# phare.net
KiCad netlist of a schematic drawn in EAGLE
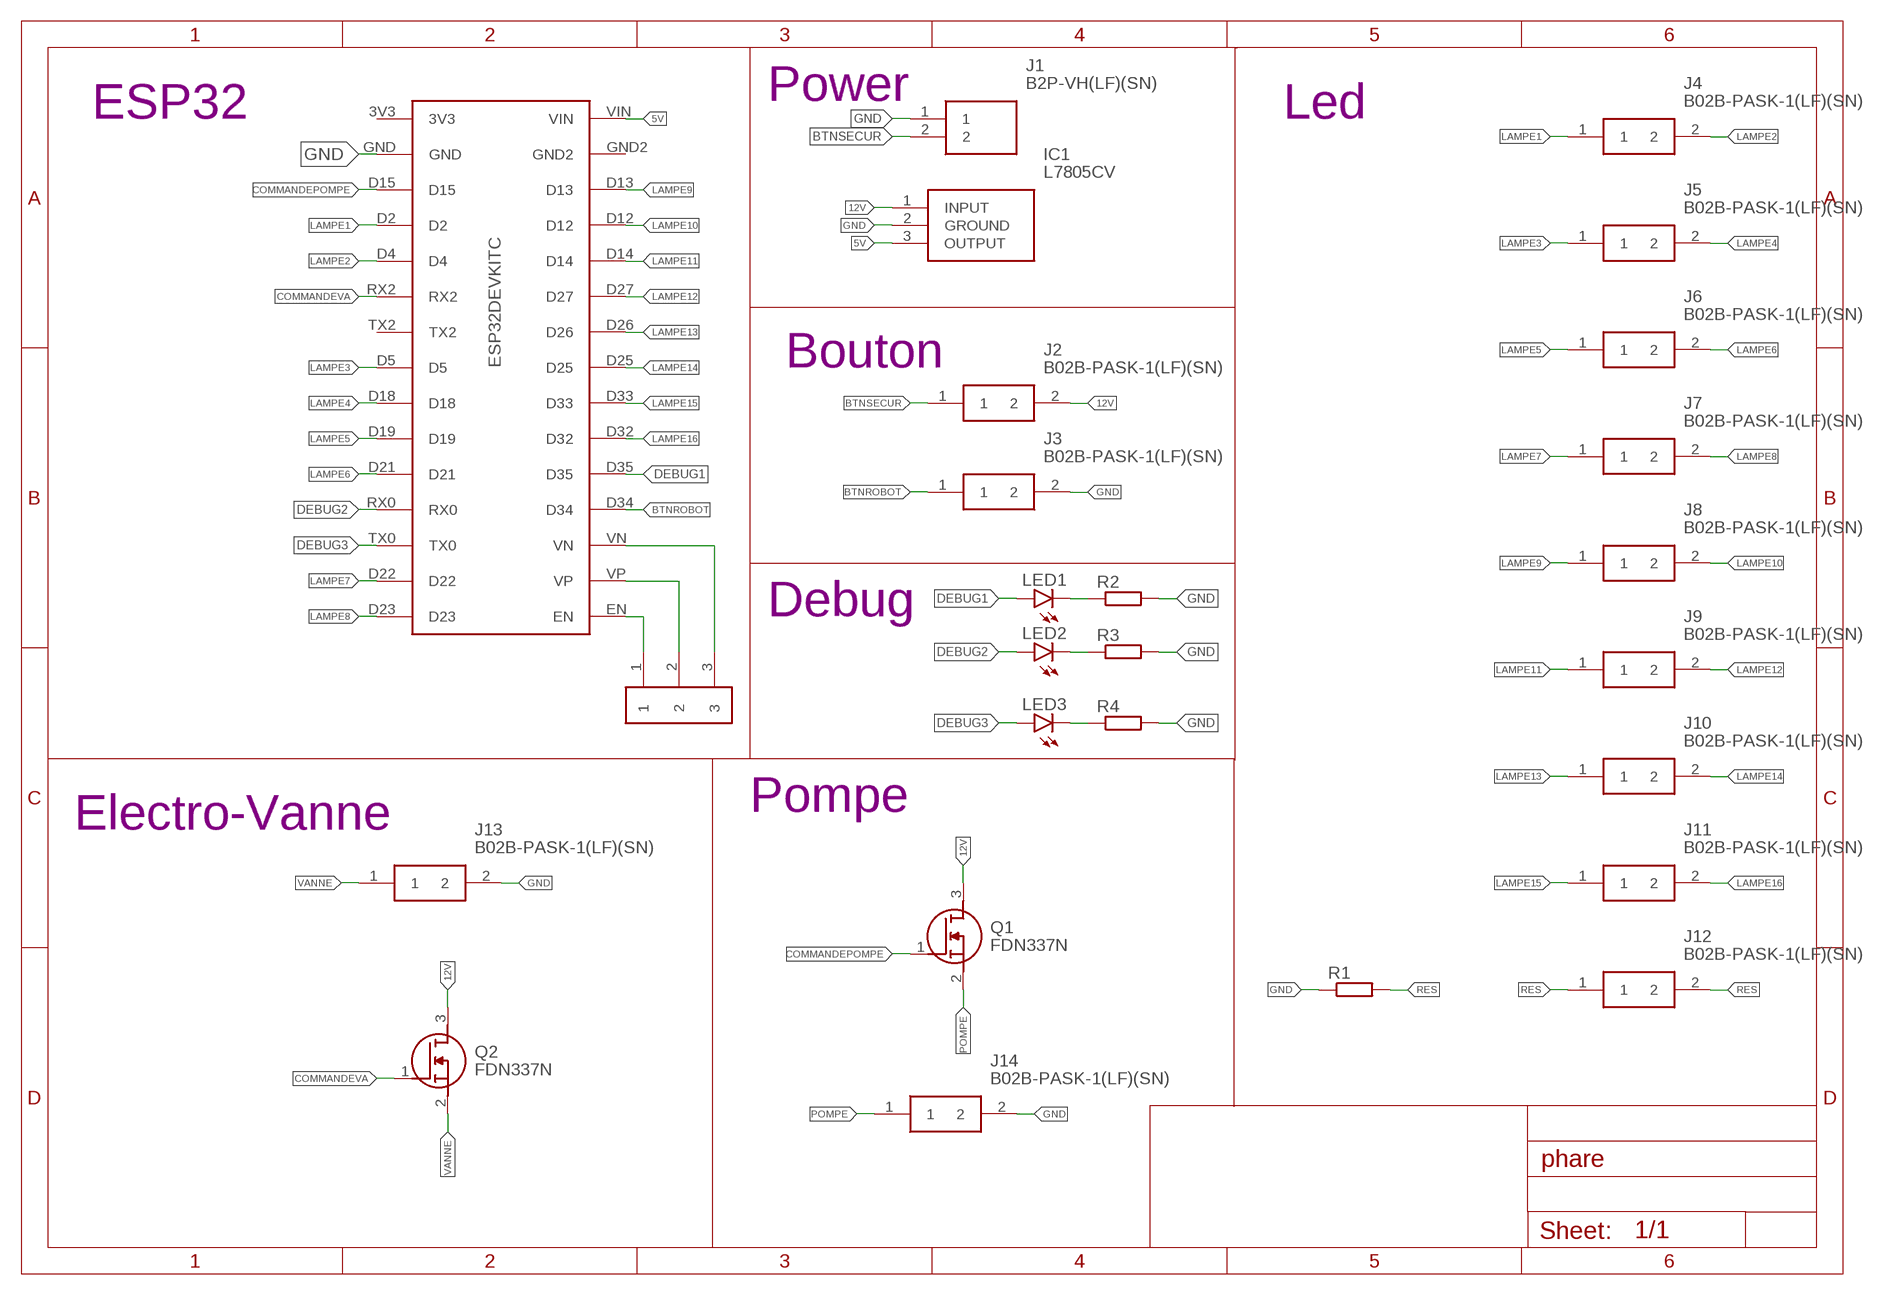
[diagram p0: schematic, sheet 1]

(export (version "E")
  (design (tool "Eeschema 10.0.6"))
  (components
    (comp (ref "IC1")
      (value "L7805CV")
      (footprint "eagle-import:TO255P460X1020X2008-3P")
      (fields (field (name "MOUSER_PART_NUMBER") "511-L7805CV"))
      (libsource (lib "eagle-import") (part "L7805CV"))
    )
    (comp (ref "J1")
      (value "B2P-VH(LF)(SN)")
      (footprint "eagle-import:SHDR2W114P0X396_1X2_786X850X94")
      (fields (field (name "RS_PART_NUMBER") "8201147P"))
      (libsource (lib "eagle-import") (part "B2P-VH(LF)(SN)"))
    )
    (comp (ref "J2")
      (value "B02B-PASK-1(LF)(SN)")
      (footprint "eagle-import:B02BPASK1LFSN")
      (libsource (lib "eagle-import") (part "B02B-PASK-1(LF)(SN)"))
    )
    (comp (ref "J3")
      (value "B02B-PASK-1(LF)(SN)")
      (footprint "eagle-import:B02BPASK1LFSN")
      (libsource (lib "eagle-import") (part "B02B-PASK-1(LF)(SN)"))
    )
    (comp (ref "J4")
      (value "B02B-PASK-1(LF)(SN)")
      (footprint "eagle-import:B02BPASK1LFSN")
      (libsource (lib "eagle-import") (part "B02B-PASK-1(LF)(SN)"))
    )
    (comp (ref "J5")
      (value "B02B-PASK-1(LF)(SN)")
      (footprint "eagle-import:B02BPASK1LFSN")
      (libsource (lib "eagle-import") (part "B02B-PASK-1(LF)(SN)"))
    )
    (comp (ref "J6")
      (value "B02B-PASK-1(LF)(SN)")
      (footprint "eagle-import:B02BPASK1LFSN")
      (libsource (lib "eagle-import") (part "B02B-PASK-1(LF)(SN)"))
    )
    (comp (ref "J7")
      (value "B02B-PASK-1(LF)(SN)")
      (footprint "eagle-import:B02BPASK1LFSN")
      (libsource (lib "eagle-import") (part "B02B-PASK-1(LF)(SN)"))
    )
    (comp (ref "J8")
      (value "B02B-PASK-1(LF)(SN)")
      (footprint "eagle-import:B02BPASK1LFSN")
      (libsource (lib "eagle-import") (part "B02B-PASK-1(LF)(SN)"))
    )
    (comp (ref "J9")
      (value "B02B-PASK-1(LF)(SN)")
      (footprint "eagle-import:B02BPASK1LFSN")
      (libsource (lib "eagle-import") (part "B02B-PASK-1(LF)(SN)"))
    )
    (comp (ref "J10")
      (value "B02B-PASK-1(LF)(SN)")
      (footprint "eagle-import:B02BPASK1LFSN")
      (libsource (lib "eagle-import") (part "B02B-PASK-1(LF)(SN)"))
    )
    (comp (ref "J11")
      (value "B02B-PASK-1(LF)(SN)")
      (footprint "eagle-import:B02BPASK1LFSN")
      (libsource (lib "eagle-import") (part "B02B-PASK-1(LF)(SN)"))
    )
    (comp (ref "J12")
      (value "B02B-PASK-1(LF)(SN)")
      (footprint "eagle-import:B02BPASK1LFSN")
      (libsource (lib "eagle-import") (part "B02B-PASK-1(LF)(SN)"))
    )
    (comp (ref "J13")
      (value "B02B-PASK-1(LF)(SN)")
      (footprint "eagle-import:B02BPASK1LFSN")
      (libsource (lib "eagle-import") (part "B02B-PASK-1(LF)(SN)"))
    )
    (comp (ref "J14")
      (value "B02B-PASK-1(LF)(SN)")
      (footprint "eagle-import:B02BPASK1LFSN")
      (libsource (lib "eagle-import") (part "B02B-PASK-1(LF)(SN)"))
    )
    (comp (ref "LED1")
      (value "LEDCHIP-LED0805")
      (footprint "eagle-import:CHIP-LED0805")
      (libsource (lib "eagle-import") (part "LEDCHIP-LED0805"))
    )
    (comp (ref "LED2")
      (value "LEDCHIP-LED0805")
      (footprint "eagle-import:CHIP-LED0805")
      (libsource (lib "eagle-import") (part "LEDCHIP-LED0805"))
    )
    (comp (ref "LED3")
      (value "LEDCHIP-LED0805")
      (footprint "eagle-import:CHIP-LED0805")
      (libsource (lib "eagle-import") (part "LEDCHIP-LED0805"))
    )
    (comp (ref "Q1")
      (value "FDN337N")
      (footprint "eagle-import:SOT95P237X112-3N")
      (fields (field (name "MOUSER_PART_NUMBER") "512-FDN337N") (field (name "RS_PART_NUMBER") "6710429P"))
      (libsource (lib "eagle-import") (part "FDN337N"))
    )
    (comp (ref "Q2")
      (value "FDN337N")
      (footprint "eagle-import:SOT95P237X112-3N")
      (fields (field (name "MOUSER_PART_NUMBER") "512-FDN337N") (field (name "RS_PART_NUMBER") "6710429P"))
      (libsource (lib "eagle-import") (part "FDN337N"))
    )
    (comp (ref "R1")
      (value "R-EU_R0805")
      (footprint "eagle-import:R0805")
      (libsource (lib "eagle-import") (part "R-EU_R0805"))
    )
    (comp (ref "R2")
      (value "R-EU_R0805")
      (footprint "eagle-import:R0805")
      (libsource (lib "eagle-import") (part "R-EU_R0805"))
    )
    (comp (ref "R3")
      (value "R-EU_R0805")
      (footprint "eagle-import:R0805")
      (libsource (lib "eagle-import") (part "R-EU_R0805"))
    )
    (comp (ref "R4")
      (value "R-EU_R0805")
      (footprint "eagle-import:R0805")
      (libsource (lib "eagle-import") (part "R-EU_R0805"))
    )
    (comp (ref "U$1")
      (value "ESP32DEVKITC")
      (footprint "eagle-import:ESP32FOOTPRINT")
      (libsource (lib "eagle-import") (part "ESP32DEVKITC"))
    )
    (comp (ref "U$2")
      (value "HEADER3PIN")
      (footprint "eagle-import:HEADER3PINFOOTPRINT")
      (libsource (lib "eagle-import") (part "HEADER3PIN"))
    )
  )
  (nets
    (net (code "1") (name "5V") (class "Default")
      (node (ref "IC1") (pin "3") (pinfunction "OUTPUT_3") (pintype "bidirectional"))
      (node (ref "U$1") (pin "VIN") (pinfunction "VIN_VIN") (pintype "bidirectional"))
    )
    (net (code "2") (name "12V") (class "Default")
      (node (ref "IC1") (pin "1") (pinfunction "INPUT_1") (pintype "bidirectional"))
      (node (ref "J2") (pin "2") (pinfunction "2_2") (pintype "bidirectional"))
      (node (ref "Q1") (pin "3") (pinfunction "D_3") (pintype "bidirectional"))
      (node (ref "Q2") (pin "3") (pinfunction "D_3") (pintype "bidirectional"))
    )
    (net (code "3") (name "BTNROBOT") (class "Default")
      (node (ref "J3") (pin "1") (pinfunction "1_1") (pintype "bidirectional"))
      (node (ref "U$1") (pin "D34") (pinfunction "D34_D34") (pintype "bidirectional"))
    )
    (net (code "4") (name "BTNSECUR") (class "Default")
      (node (ref "J1") (pin "2") (pinfunction "2_2") (pintype "bidirectional"))
      (node (ref "J2") (pin "1") (pinfunction "1_1") (pintype "bidirectional"))
    )
    (net (code "5") (name "COMMANDEPOMPE") (class "Default")
      (node (ref "Q1") (pin "1") (pinfunction "G_1") (pintype "bidirectional"))
      (node (ref "U$1") (pin "D15") (pinfunction "D15_D15") (pintype "bidirectional"))
    )
    (net (code "6") (name "COMMANDEVA") (class "Default")
      (node (ref "Q2") (pin "1") (pinfunction "G_1") (pintype "bidirectional"))
      (node (ref "U$1") (pin "RX2") (pinfunction "RX2_RX2") (pintype "bidirectional"))
    )
    (net (code "7") (name "DEBUG1") (class "Default")
      (node (ref "LED1") (pin "A") (pinfunction "A_A") (pintype "passive"))
      (node (ref "U$1") (pin "D35") (pinfunction "D35_D35") (pintype "bidirectional"))
    )
    (net (code "8") (name "DEBUG2") (class "Default")
      (node (ref "LED2") (pin "A") (pinfunction "A_A") (pintype "passive"))
      (node (ref "U$1") (pin "RX0") (pinfunction "RX0_RX0") (pintype "bidirectional"))
    )
    (net (code "9") (name "DEBUG3") (class "Default")
      (node (ref "LED3") (pin "A") (pinfunction "A_A") (pintype "passive"))
      (node (ref "U$1") (pin "TX0") (pinfunction "TX0_TX0") (pintype "bidirectional"))
    )
    (net (code "10") (name "GND") (class "Default")
      (node (ref "IC1") (pin "2") (pinfunction "GROUND_2") (pintype "bidirectional"))
      (node (ref "J1") (pin "1") (pinfunction "1_1") (pintype "bidirectional"))
      (node (ref "J13") (pin "2") (pinfunction "2_2") (pintype "bidirectional"))
      (node (ref "J14") (pin "2") (pinfunction "2_2") (pintype "bidirectional"))
      (node (ref "J3") (pin "2") (pinfunction "2_2") (pintype "bidirectional"))
      (node (ref "R1") (pin "1") (pinfunction "1_1") (pintype "passive"))
      (node (ref "R2") (pin "2") (pinfunction "2_2") (pintype "passive"))
      (node (ref "R3") (pin "2") (pinfunction "2_2") (pintype "passive"))
      (node (ref "R4") (pin "2") (pinfunction "2_2") (pintype "passive"))
      (node (ref "U$1") (pin "GND") (pinfunction "GND_GND") (pintype "bidirectional"))
    )
    (net (code "11") (name "LAMPE1") (class "Default")
      (node (ref "J4") (pin "1") (pinfunction "1_1") (pintype "bidirectional"))
      (node (ref "U$1") (pin "D2") (pinfunction "D2_D2") (pintype "bidirectional"))
    )
    (net (code "12") (name "LAMPE2") (class "Default")
      (node (ref "J4") (pin "2") (pinfunction "2_2") (pintype "bidirectional"))
      (node (ref "U$1") (pin "D4") (pinfunction "D4_D4") (pintype "bidirectional"))
    )
    (net (code "13") (name "LAMPE3") (class "Default")
      (node (ref "J5") (pin "1") (pinfunction "1_1") (pintype "bidirectional"))
      (node (ref "U$1") (pin "D5") (pinfunction "D5_D5") (pintype "bidirectional"))
    )
    (net (code "14") (name "LAMPE4") (class "Default")
      (node (ref "J5") (pin "2") (pinfunction "2_2") (pintype "bidirectional"))
      (node (ref "U$1") (pin "D18") (pinfunction "D18_D18") (pintype "bidirectional"))
    )
    (net (code "15") (name "LAMPE5") (class "Default")
      (node (ref "J6") (pin "1") (pinfunction "1_1") (pintype "bidirectional"))
      (node (ref "U$1") (pin "D19") (pinfunction "D19_D19") (pintype "bidirectional"))
    )
    (net (code "16") (name "LAMPE6") (class "Default")
      (node (ref "J6") (pin "2") (pinfunction "2_2") (pintype "bidirectional"))
      (node (ref "U$1") (pin "D21") (pinfunction "D21_D21") (pintype "bidirectional"))
    )
    (net (code "17") (name "LAMPE7") (class "Default")
      (node (ref "J7") (pin "1") (pinfunction "1_1") (pintype "bidirectional"))
      (node (ref "U$1") (pin "D22") (pinfunction "D22_D22") (pintype "bidirectional"))
    )
    (net (code "18") (name "LAMPE8") (class "Default")
      (node (ref "J7") (pin "2") (pinfunction "2_2") (pintype "bidirectional"))
      (node (ref "U$1") (pin "D23") (pinfunction "D23_D23") (pintype "bidirectional"))
    )
    (net (code "19") (name "LAMPE9") (class "Default")
      (node (ref "J8") (pin "1") (pinfunction "1_1") (pintype "bidirectional"))
      (node (ref "U$1") (pin "D13") (pinfunction "D13_D13") (pintype "bidirectional"))
    )
    (net (code "20") (name "LAMPE10") (class "Default")
      (node (ref "J8") (pin "2") (pinfunction "2_2") (pintype "bidirectional"))
      (node (ref "U$1") (pin "D12") (pinfunction "D12_D12") (pintype "bidirectional"))
    )
    (net (code "21") (name "LAMPE11") (class "Default")
      (node (ref "J9") (pin "1") (pinfunction "1_1") (pintype "bidirectional"))
      (node (ref "U$1") (pin "D14") (pinfunction "D14_D14") (pintype "bidirectional"))
    )
    (net (code "22") (name "LAMPE12") (class "Default")
      (node (ref "J9") (pin "2") (pinfunction "2_2") (pintype "bidirectional"))
      (node (ref "U$1") (pin "D27") (pinfunction "D27_D27") (pintype "bidirectional"))
    )
    (net (code "23") (name "LAMPE13") (class "Default")
      (node (ref "J10") (pin "1") (pinfunction "1_1") (pintype "bidirectional"))
      (node (ref "U$1") (pin "D26") (pinfunction "D26_D26") (pintype "bidirectional"))
    )
    (net (code "24") (name "LAMPE14") (class "Default")
      (node (ref "J10") (pin "2") (pinfunction "2_2") (pintype "bidirectional"))
      (node (ref "U$1") (pin "D25") (pinfunction "D25_D25") (pintype "bidirectional"))
    )
    (net (code "25") (name "LAMPE15") (class "Default")
      (node (ref "J11") (pin "1") (pinfunction "1_1") (pintype "bidirectional"))
      (node (ref "U$1") (pin "D33") (pinfunction "D33_D33") (pintype "bidirectional"))
    )
    (net (code "26") (name "LAMPE16") (class "Default")
      (node (ref "J11") (pin "2") (pinfunction "2_2") (pintype "bidirectional"))
      (node (ref "U$1") (pin "D32") (pinfunction "D32_D32") (pintype "bidirectional"))
    )
    (net (code "27") (name "Net-(LED1-PadC)") (class "Default")
      (node (ref "LED1") (pin "C") (pinfunction "C_C") (pintype "passive"))
      (node (ref "R2") (pin "1") (pinfunction "1_1") (pintype "passive"))
    )
    (net (code "28") (name "Net-(LED2-PadC)") (class "Default")
      (node (ref "LED2") (pin "C") (pinfunction "C_C") (pintype "passive"))
      (node (ref "R3") (pin "1") (pinfunction "1_1") (pintype "passive"))
    )
    (net (code "29") (name "Net-(LED3-PadC)") (class "Default")
      (node (ref "LED3") (pin "C") (pinfunction "C_C") (pintype "passive"))
      (node (ref "R4") (pin "1") (pinfunction "1_1") (pintype "passive"))
    )
    (net (code "30") (name "Net-(U$1-PadEN)") (class "Default")
      (node (ref "U$1") (pin "EN") (pinfunction "EN_EN") (pintype "bidirectional"))
      (node (ref "U$2") (pin "1") (pinfunction "1_1") (pintype "bidirectional"))
    )
    (net (code "31") (name "Net-(U$1-PadVN)") (class "Default")
      (node (ref "U$1") (pin "VN") (pinfunction "VN_VN") (pintype "bidirectional"))
      (node (ref "U$2") (pin "3") (pinfunction "3_3") (pintype "bidirectional"))
    )
    (net (code "32") (name "Net-(U$1-PadVP)") (class "Default")
      (node (ref "U$1") (pin "VP") (pinfunction "VP_VP") (pintype "bidirectional"))
      (node (ref "U$2") (pin "2") (pinfunction "2_2") (pintype "bidirectional"))
    )
    (net (code "33") (name "POMPE") (class "Default")
      (node (ref "J14") (pin "1") (pinfunction "1_1") (pintype "bidirectional"))
      (node (ref "Q1") (pin "2") (pinfunction "S_2") (pintype "bidirectional"))
    )
    (net (code "34") (name "RES") (class "Default")
      (node (ref "J12") (pin "1") (pinfunction "1_1") (pintype "bidirectional"))
      (node (ref "J12") (pin "2") (pinfunction "2_2") (pintype "bidirectional"))
      (node (ref "R1") (pin "2") (pinfunction "2_2") (pintype "passive"))
    )
    (net (code "35") (name "VANNE") (class "Default")
      (node (ref "J13") (pin "1") (pinfunction "1_1") (pintype "bidirectional"))
      (node (ref "Q2") (pin "2") (pinfunction "S_2") (pintype "bidirectional"))
    )
    (net (code "36") (name "unconnected-(U$1-Pad3V3)") (class "Default")
      (node (ref "U$1") (pin "3V3") (pinfunction "3V3_3V3") (pintype "bidirectional"))
    )
    (net (code "37") (name "unconnected-(U$1-PadGND2)") (class "Default")
      (node (ref "U$1") (pin "GND2") (pinfunction "GND2_GND2") (pintype "bidirectional"))
    )
    (net (code "38") (name "unconnected-(U$1-PadTX2)") (class "Default")
      (node (ref "U$1") (pin "TX2") (pinfunction "TX2_TX2") (pintype "bidirectional"))
    )
  )
)
